# Transceiver.net
KiCad netlist of a schematic drawn in EAGLE
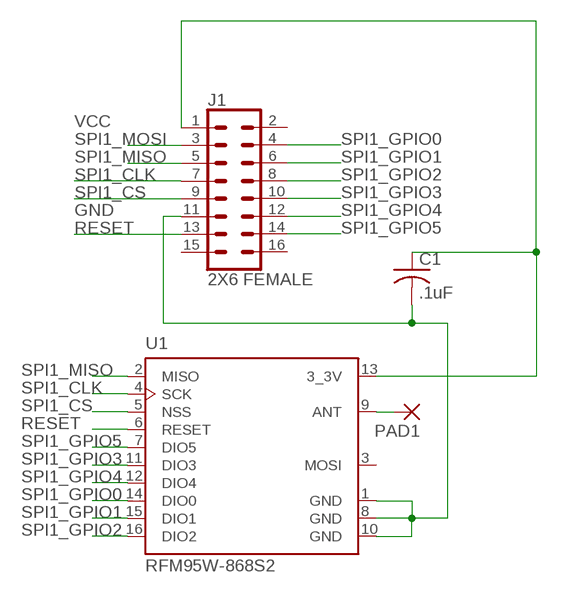
[diagram p0: schematic, sheet 1]

(export (version "E")
  (design (tool "Eeschema 10.0.6"))
  (components
    (comp (ref "C1")
      (value ".1uF")
      (footprint "eagle-import:C1206")
      (libsource (lib "eagle-import") (part "C-ALL_PACKAGESC1206"))
    )
    (comp (ref "J1")
      (value "2X6 FEMALE")
      (footprint "eagle-import:2X7")
      (libsource (lib "eagle-import") (part "SENSOR_BREAKOUTPTH_FEMALE"))
    )
    (comp (ref "PAD1")
      (value "2,54/1,0")
      (footprint "eagle-import:2,54_1,0")
      (libsource (lib "eagle-import") (part "2,54/1,0"))
    )
    (comp (ref "U1")
      (value "RFM95W-868S2")
      (footprint "eagle-import:XCVR_RFM95W-868S2")
      (fields (field (name "MF") "RF"))
      (libsource (lib "eagle-import") (part "RFM95W-868S2"))
    )
  )
  (nets
    (net (code "1") (name "/GND") (class "Default")
      (node (ref "C1") (pin "2") (pinfunction "2_2") (pintype "passive"))
      (node (ref "J1") (pin "11") (pinfunction "11_11") (pintype "passive"))
      (node (ref "U1") (pin "1") (pinfunction "GND_1") (pintype "power_in"))
      (node (ref "U1") (pin "10") (pinfunction "GND_10") (pintype "power_in"))
      (node (ref "U1") (pin "8") (pinfunction "GND_8") (pintype "power_in"))
    )
    (net (code "2") (name "/RESET") (class "Default")
      (node (ref "J1") (pin "13") (pinfunction "13_13") (pintype "passive"))
      (node (ref "U1") (pin "6") (pinfunction "RESET_6") (pintype "bidirectional"))
    )
    (net (code "3") (name "/SPI1_CLK") (class "Default")
      (node (ref "J1") (pin "7") (pinfunction "7_7") (pintype "passive"))
      (node (ref "U1") (pin "4") (pinfunction "SCK_4") (pintype "input"))
    )
    (net (code "4") (name "/SPI1_CS") (class "Default")
      (node (ref "J1") (pin "9") (pinfunction "9_9") (pintype "passive"))
      (node (ref "U1") (pin "5") (pinfunction "NSS_5") (pintype "input"))
    )
    (net (code "5") (name "/SPI1_GPIO0") (class "Default")
      (node (ref "J1") (pin "4") (pinfunction "4_4") (pintype "passive"))
      (node (ref "U1") (pin "14") (pinfunction "DIO0_14") (pintype "bidirectional"))
    )
    (net (code "6") (name "/SPI1_GPIO1") (class "Default")
      (node (ref "J1") (pin "6") (pinfunction "6_6") (pintype "passive"))
      (node (ref "U1") (pin "15") (pinfunction "DIO1_15") (pintype "bidirectional"))
    )
    (net (code "7") (name "/SPI1_GPIO2") (class "Default")
      (node (ref "J1") (pin "8") (pinfunction "8_8") (pintype "passive"))
      (node (ref "U1") (pin "16") (pinfunction "DIO2_16") (pintype "bidirectional"))
    )
    (net (code "8") (name "/SPI1_GPIO3") (class "Default")
      (node (ref "J1") (pin "10") (pinfunction "10_10") (pintype "passive"))
      (node (ref "U1") (pin "11") (pinfunction "DIO3_11") (pintype "bidirectional"))
    )
    (net (code "9") (name "/SPI1_GPIO4") (class "Default")
      (node (ref "J1") (pin "12") (pinfunction "12_12") (pintype "passive"))
      (node (ref "U1") (pin "12") (pinfunction "DIO4_12") (pintype "bidirectional"))
    )
    (net (code "10") (name "/SPI1_GPIO5") (class "Default")
      (node (ref "J1") (pin "14") (pinfunction "14_14") (pintype "passive"))
      (node (ref "U1") (pin "7") (pinfunction "DIO5_7") (pintype "bidirectional"))
    )
    (net (code "11") (name "/SPI1_MISO") (class "Default")
      (node (ref "J1") (pin "5") (pinfunction "5_5") (pintype "passive"))
      (node (ref "U1") (pin "2") (pinfunction "MISO_2") (pintype "input"))
    )
    (net (code "12") (name "/SPI1_MOSI") (class "Default")
      (node (ref "J1") (pin "3") (pinfunction "3_3") (pintype "passive"))
    )
    (net (code "13") (name "/VCC") (class "Default")
      (node (ref "C1") (pin "1") (pinfunction "1_1") (pintype "passive"))
      (node (ref "J1") (pin "1") (pinfunction "1_1") (pintype "passive"))
      (node (ref "U1") (pin "13") (pinfunction "3_3V_13") (pintype "power_in"))
    )
    (net (code "14") (name "Net-(PAD1-P)") (class "Default")
      (node (ref "PAD1") (pin "1") (pinfunction "P_1") (pintype "passive"))
      (node (ref "U1") (pin "9") (pinfunction "ANT_9") (pintype "passive"))
    )
    (net (code "15") (name "unconnected-(J1-Pad2)") (class "Default")
      (node (ref "J1") (pin "2") (pinfunction "2_2") (pintype "passive"))
    )
    (net (code "16") (name "unconnected-(J1-Pad15)") (class "Default")
      (node (ref "J1") (pin "15") (pinfunction "15_15") (pintype "passive"))
    )
    (net (code "17") (name "unconnected-(J1-Pad16)") (class "Default")
      (node (ref "J1") (pin "16") (pinfunction "16_16") (pintype "passive"))
    )
    (net (code "18") (name "unconnected-(U1-MOSI-Pad3)") (class "Default")
      (node (ref "U1") (pin "3") (pinfunction "MOSI_3") (pintype "output"))
    )
  )
)
